# Top.net
KiCad netlist of a schematic drawn in Altium Designer
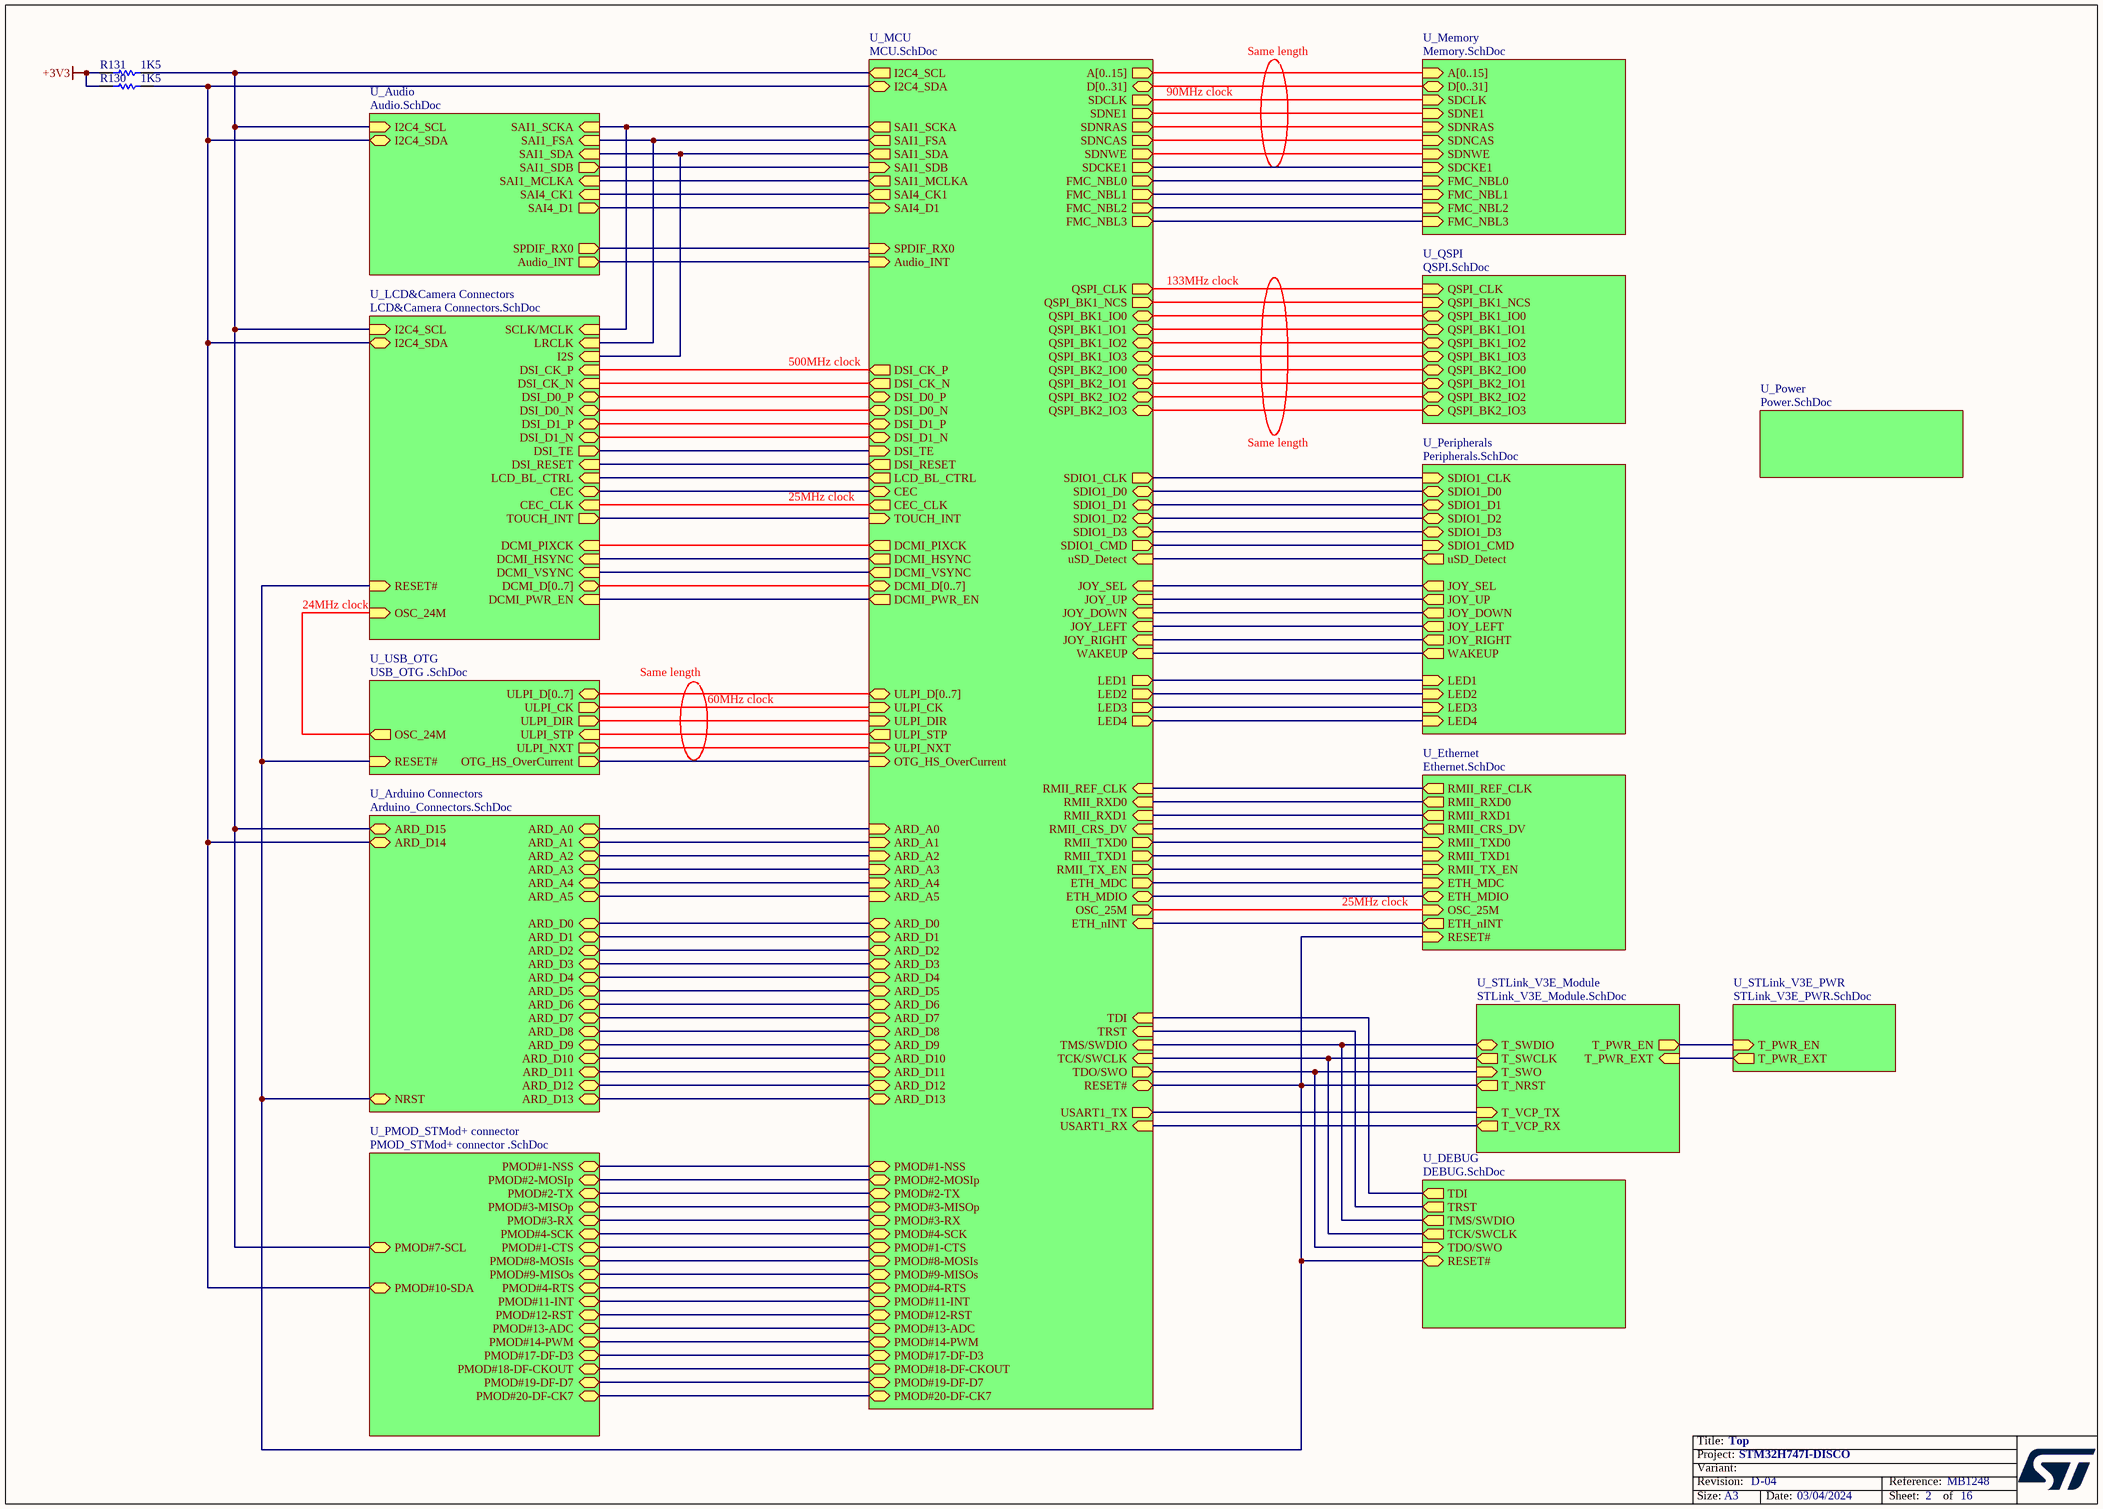
[diagram p0: Top.SchDoc]

(export (version "E")
  (design (tool "Eeschema 10.0.6"))
  (components
    (comp (ref "R130")
      (value "1K5")
      (footprint "0603R")
      (description "Resistor")
      (fields (field (name "PUBLISHER") "Altium Limited"))
      (libsource (lib "Miscellaneous Devices") (part "Res1"))
    )
    (comp (ref "R131")
      (value "1K5")
      (footprint "0603R")
      (description "Resistor")
      (fields (field (name "PUBLISHER") "Altium Limited"))
      (libsource (lib "Miscellaneous Devices") (part "Res1"))
    )
  )
  (nets
    (net (code "1") (name "+3V3") (class "Default")
      (node (ref "R130") (pin "1") (pinfunction "1_1") (pintype "passive"))
      (node (ref "R131") (pin "1") (pinfunction "1_1") (pintype "passive"))
    )
    (net (code "22") (name "/ARD_D14") (class "Default")
      (node (ref "R130") (pin "2") (pinfunction "2_2") (pintype "passive"))
    )
    (net (code "48") (name "/I2C4_SCL") (class "Default")
      (node (ref "R131") (pin "2") (pinfunction "2_2") (pintype "passive"))
    )
  )
)
